# 2_Rotary_Encoder_IC.net
KiCad netlist of a schematic drawn in Altium Designer
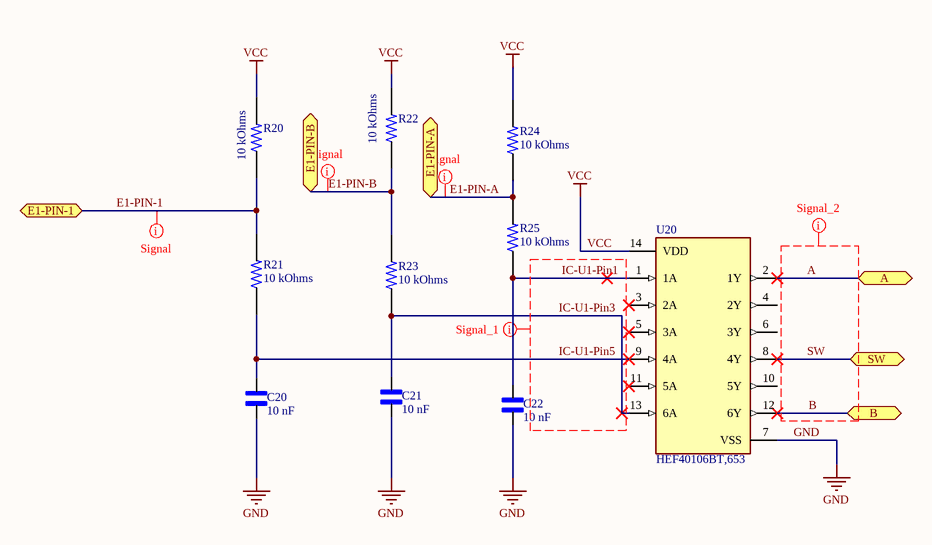
[diagram p0: 2_Rotary_Encoder_IC.SchDoc]

(export (version "E")
  (design (tool "Eeschema 10.0.6"))
  (components
    (comp (ref "C20")
      (value "10 nF")
      (footprint "C-0603")
      (description "Ceramic Capacitor 16V 0603 (1608 Metric)")
      (fields (field (name "MP") "C0603C104J4RAC") (field (name "MF") "KEMET"))
      (libsource (lib "Rotary_Encoder") (part "C-0603"))
    )
    (comp (ref "C21")
      (value "10 nF")
      (footprint "C-0603")
      (description "Ceramic Capacitor 16V 0603 (1608 Metric)")
      (fields (field (name "MP") "C0603C104J4RAC") (field (name "MF") "KEMET"))
      (libsource (lib "Rotary_Encoder") (part "C-0603"))
    )
    (comp (ref "C22")
      (value "10 nF")
      (footprint "C-0603")
      (description "Ceramic Capacitor 16V 0603 (1608 Metric)")
      (fields (field (name "MP") "C0603C104J4RAC") (field (name "MF") "KEMET"))
      (libsource (lib "Rotary_Encoder") (part "C-0603"))
    )
    (comp (ref "R20")
      (value "10 kOhms")
      (footprint "R-0603")
      (description "0603")
      (fields (field (name "MP") "2-1623703-0") (field (name "TOLERANCE") "1%"))
      (libsource (lib "Rotary_Encoder") (part "R-0603"))
    )
    (comp (ref "R21")
      (value "10 kOhms")
      (footprint "R-0603")
      (description "0603")
      (fields (field (name "MP") "2-1623703-0") (field (name "TOLERANCE") "1%"))
      (libsource (lib "Rotary_Encoder") (part "R-0603"))
    )
    (comp (ref "R22")
      (value "10 kOhms")
      (footprint "R-0603")
      (description "0603")
      (fields (field (name "MP") "2-1623703-0") (field (name "TOLERANCE") "1%"))
      (libsource (lib "Rotary_Encoder") (part "R-0603"))
    )
    (comp (ref "R23")
      (value "10 kOhms")
      (footprint "R-0603")
      (description "0603")
      (fields (field (name "MP") "2-1623703-0") (field (name "TOLERANCE") "1%"))
      (libsource (lib "Rotary_Encoder") (part "R-0603"))
    )
    (comp (ref "R24")
      (value "10 kOhms")
      (footprint "R-0603")
      (description "0603")
      (fields (field (name "MP") "2-1623703-0") (field (name "TOLERANCE") "1%"))
      (libsource (lib "Rotary_Encoder") (part "R-0603"))
    )
    (comp (ref "R25")
      (value "10 kOhms")
      (footprint "R-0603")
      (description "0603")
      (fields (field (name "MP") "2-1623703-0") (field (name "TOLERANCE") "1%"))
      (libsource (lib "Rotary_Encoder") (part "R-0603"))
    )
    (comp (ref "U20")
      (value "HEF40106BT,653")
      (footprint "FP-SOT108-1-IPC_A")
      (description "IC INVERT SCHMITT 6CH 6-INP 14SO")
      (libsource (lib "Rotary_Encoder") (part "CD4016B"))
    )
  )
  (nets
    (net (code "1") (name "/A") (class "Default")
      (node (ref "U20") (pin "2") (pinfunction "1Y_2") (pintype "output+no_connect"))
    )
    (net (code "2") (name "/B") (class "Default")
      (node (ref "U20") (pin "12") (pinfunction "6Y_12") (pintype "output+no_connect"))
    )
    (net (code "3") (name "/E1-PIN-1") (class "Default")
      (node (ref "R20") (pin "1") (pinfunction "1_1") (pintype "passive"))
      (node (ref "R21") (pin "2") (pinfunction "2_2") (pintype "passive"))
    )
    (net (code "4") (name "/E1-PIN-A") (class "Default")
      (node (ref "R24") (pin "1") (pinfunction "1_1") (pintype "passive"))
      (node (ref "R25") (pin "2") (pinfunction "2_2") (pintype "passive"))
    )
    (net (code "5") (name "/E1-PIN-B") (class "Default")
      (node (ref "R22") (pin "1") (pinfunction "1_1") (pintype "passive"))
      (node (ref "R23") (pin "2") (pinfunction "2_2") (pintype "passive"))
    )
    (net (code "6") (name "/IC-U1-Pin1") (class "Default")
      (node (ref "C22") (pin "2") (pinfunction "2_2") (pintype "passive"))
      (node (ref "R25") (pin "1") (pinfunction "1_1") (pintype "passive"))
      (node (ref "U20") (pin "1") (pinfunction "1A_1") (pintype "input"))
    )
    (net (code "7") (name "/IC-U1-Pin3") (class "Default")
      (node (ref "C21") (pin "2") (pinfunction "2_2") (pintype "passive"))
      (node (ref "R23") (pin "1") (pinfunction "1_1") (pintype "passive"))
      (node (ref "U20") (pin "13") (pinfunction "6A_13") (pintype "input"))
    )
    (net (code "8") (name "/IC-U1-Pin5") (class "Default")
      (node (ref "C20") (pin "2") (pinfunction "2_2") (pintype "passive"))
      (node (ref "R21") (pin "1") (pinfunction "1_1") (pintype "passive"))
      (node (ref "U20") (pin "9") (pinfunction "4A_9") (pintype "input"))
    )
    (net (code "9") (name "/SW") (class "Default")
      (node (ref "U20") (pin "8") (pinfunction "4Y_8") (pintype "output+no_connect"))
    )
    (net (code "10") (name "GND") (class "Default")
      (node (ref "C20") (pin "1") (pinfunction "1_1") (pintype "passive"))
      (node (ref "C21") (pin "1") (pinfunction "1_1") (pintype "passive"))
      (node (ref "C22") (pin "1") (pinfunction "1_1") (pintype "passive"))
      (node (ref "U20") (pin "7") (pinfunction "VSS_7") (pintype "power_in"))
    )
    (net (code "11") (name "VCC") (class "Default")
      (node (ref "R20") (pin "2") (pinfunction "2_2") (pintype "passive"))
      (node (ref "R22") (pin "2") (pinfunction "2_2") (pintype "passive"))
      (node (ref "R24") (pin "2") (pinfunction "2_2") (pintype "passive"))
      (node (ref "U20") (pin "14") (pinfunction "VDD_14") (pintype "power_in"))
    )
    (net (code "12") (name "unconnected-(U20-2A-Pad3)") (class "Default")
      (node (ref "U20") (pin "3") (pinfunction "2A_3") (pintype "input+no_connect"))
    )
    (net (code "13") (name "unconnected-(U20-2Y-Pad4)") (class "Default")
      (node (ref "U20") (pin "4") (pinfunction "2Y_4") (pintype "output"))
    )
    (net (code "14") (name "unconnected-(U20-3A-Pad5)") (class "Default")
      (node (ref "U20") (pin "5") (pinfunction "3A_5") (pintype "input+no_connect"))
    )
    (net (code "15") (name "unconnected-(U20-3Y-Pad6)") (class "Default")
      (node (ref "U20") (pin "6") (pinfunction "3Y_6") (pintype "output"))
    )
    (net (code "16") (name "unconnected-(U20-5A-Pad11)") (class "Default")
      (node (ref "U20") (pin "11") (pinfunction "5A_11") (pintype "input+no_connect"))
    )
    (net (code "17") (name "unconnected-(U20-5Y-Pad10)") (class "Default")
      (node (ref "U20") (pin "10") (pinfunction "5Y_10") (pintype "output"))
    )
  )
)
